# Voltage_Sensor.net
KiCad netlist of a schematic drawn in Altium Designer
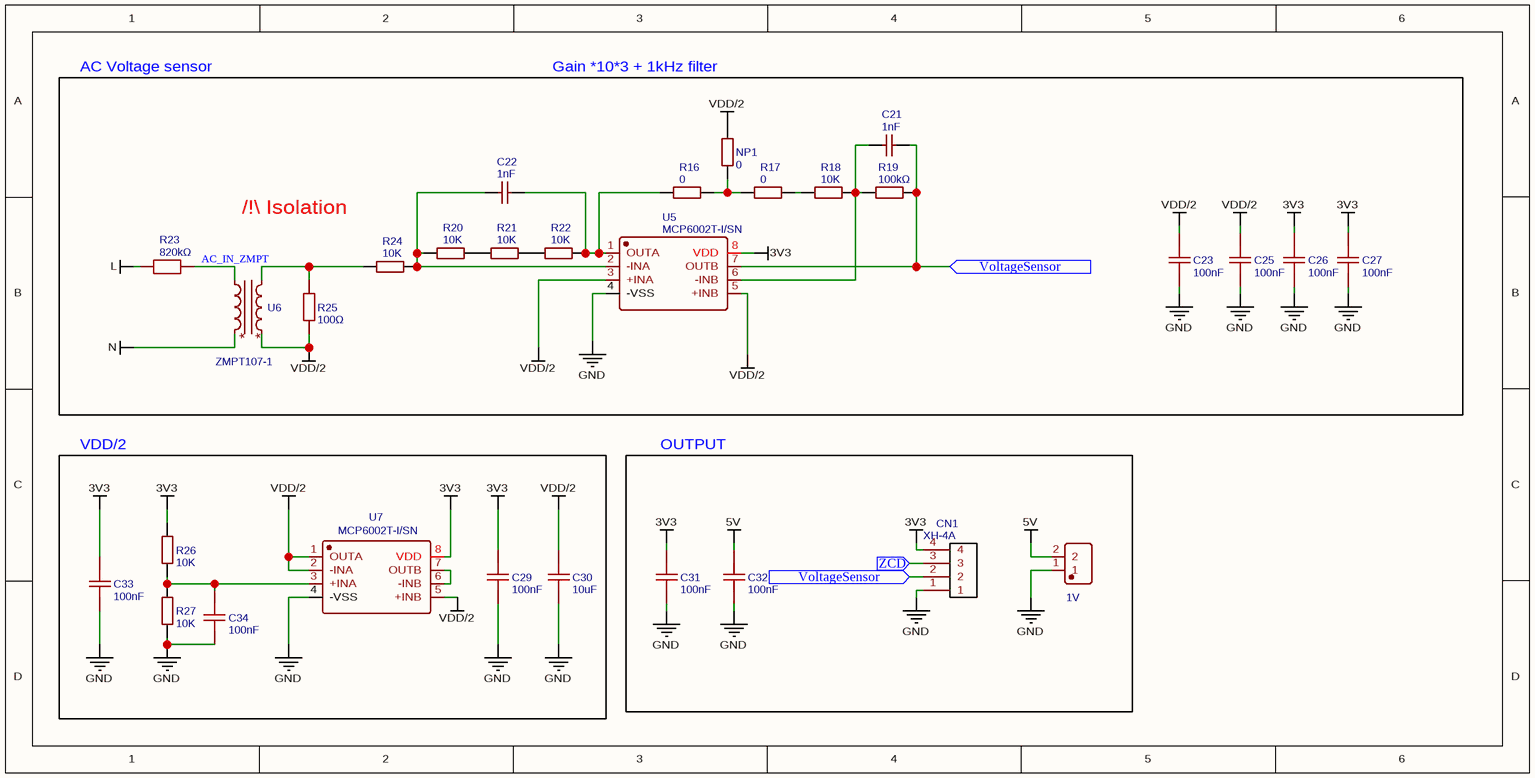
[diagram p0: Voltage Sensor.schdoc]

(export (version "E")
  (design (tool "Eeschema 10.0.6"))
  (components
    (comp (ref "1V")
      (value "XH-2A_C2908600")
      (fields
        (field (name "BOM_SUPPLIER PART") "C2908600")
        (field (name "BOM_MANUFACTURER PART") "XH-2A")
        (field (name "CONTRIBUTOR") "LCSC")
      )
      (libsource (lib "altium-import") (part "root_0_XH-2A_C2908600_"))
    )
    (comp (ref "C21")
      (value "1nF")
      (fields
        (field (name "BOM_MANUFACTURER PART") "CL10B102KB8NNNC")
        (field (name "BOM_SUPPLIER PART") "C1588")
      )
      (libsource (lib "altium-import") (part "root_0_1nF_"))
    )
    (comp (ref "C22")
      (value "1nF")
      (fields
        (field (name "BOM_MANUFACTURER PART") "CL10B102KB8NNNC")
        (field (name "BOM_SUPPLIER PART") "C1588")
      )
      (libsource (lib "altium-import") (part "root_0_1nF_"))
    )
    (comp (ref "C23")
      (value "100nF")
      (fields
        (field (name "BOM_MANUFACTURER PART") "CL10B104KB8NNNC")
        (field (name "BOM_SUPPLIER PART") "C1591")
      )
      (libsource (lib "altium-import") (part "root_3_100nF_"))
    )
    (comp (ref "C25")
      (value "100nF")
      (fields
        (field (name "BOM_MANUFACTURER PART") "CL10B104KB8NNNC")
        (field (name "BOM_SUPPLIER PART") "C1591")
      )
      (libsource (lib "altium-import") (part "root_3_100nF_"))
    )
    (comp (ref "C26")
      (value "100nF")
      (fields
        (field (name "BOM_MANUFACTURER PART") "CL10B104KB8NNNC")
        (field (name "BOM_SUPPLIER PART") "C1591")
      )
      (libsource (lib "altium-import") (part "root_3_100nF_"))
    )
    (comp (ref "C27")
      (value "100nF")
      (fields
        (field (name "BOM_MANUFACTURER PART") "CL10B104KB8NNNC")
        (field (name "BOM_SUPPLIER PART") "C1591")
      )
      (libsource (lib "altium-import") (part "root_3_100nF_"))
    )
    (comp (ref "C29")
      (value "100nF")
      (fields
        (field (name "BOM_MANUFACTURER PART") "CL10B104KB8NNNC")
        (field (name "BOM_SUPPLIER PART") "C1591")
      )
      (libsource (lib "altium-import") (part "root_3_100nF_"))
    )
    (comp (ref "C30")
      (value "10uF")
      (fields
        (field (name "BOM_MANUFACTURER PART") "0805F106M160NT")
        (field (name "BOM_SUPPLIER PART") "C90545")
      )
      (libsource (lib "altium-import") (part "root_1_10uF_"))
    )
    (comp (ref "C31")
      (value "100nF")
      (fields
        (field (name "BOM_MANUFACTURER PART") "CL10B104KB8NNNC")
        (field (name "BOM_SUPPLIER PART") "C1591")
      )
      (libsource (lib "altium-import") (part "root_3_100nF_"))
    )
    (comp (ref "C32")
      (value "100nF")
      (fields
        (field (name "BOM_MANUFACTURER PART") "CL10B104KB8NNNC")
        (field (name "BOM_SUPPLIER PART") "C1591")
      )
      (libsource (lib "altium-import") (part "root_3_100nF_"))
    )
    (comp (ref "C33")
      (value "100nF")
      (fields
        (field (name "BOM_MANUFACTURER PART") "CL10B104KB8NNNC")
        (field (name "BOM_SUPPLIER PART") "C1591")
      )
      (libsource (lib "altium-import") (part "root_3_100nF_"))
    )
    (comp (ref "C34")
      (value "100nF")
      (fields
        (field (name "BOM_MANUFACTURER PART") "CL10B104KB8NNNC")
        (field (name "BOM_SUPPLIER PART") "C1591")
      )
      (libsource (lib "altium-import") (part "root_3_100nF_"))
    )
    (comp (ref "CN1")
      (value "XH-4A")
      (fields (field (name "BOM_SUPPLIER PART") "C37815"))
      (libsource (lib "altium-import") (part "root_2_XH-4A_"))
    )
    (comp (ref "NP1")
      (value "0")
      (fields
        (field (name "BOM_MANUFACTURER PART") "RC0603JR-070RL")
        (field (name "BOM_SUPPLIER PART") "C95177")
      )
      (libsource (lib "altium-import") (part "root_1_0_"))
    )
    (comp (ref "R16")
      (value "0")
      (fields
        (field (name "BOM_MANUFACTURER PART") "RC0603JR-070RL")
        (field (name "BOM_SUPPLIER PART") "C95177")
      )
      (libsource (lib "altium-import") (part "root_0_0_"))
    )
    (comp (ref "R17")
      (value "0")
      (fields
        (field (name "BOM_MANUFACTURER PART") "RC0603JR-070RL")
        (field (name "BOM_SUPPLIER PART") "C95177")
      )
      (libsource (lib "altium-import") (part "root_0_0_"))
    )
    (comp (ref "R18")
      (value "10K")
      (fields
        (field (name "BOM_MANUFACTURER PART") "RC0603FR-0710KL")
        (field (name "BOM_SUPPLIER PART") "C98220")
      )
      (libsource (lib "altium-import") (part "root_0_10K_"))
    )
    (comp (ref "R19")
      (value "100kΩ")
      (fields
        (field (name "BOM_MANUFACTURER PART") "RTT031003FTP")
        (field (name "BOM_SUPPLIER PART") "C103200")
      )
      (libsource (lib "altium-import") (part "root_2_100kΩ_"))
    )
    (comp (ref "R20")
      (value "10K")
      (fields
        (field (name "BOM_MANUFACTURER PART") "RC0603FR-0710KL")
        (field (name "BOM_SUPPLIER PART") "C98220")
      )
      (libsource (lib "altium-import") (part "root_0_10K_"))
    )
    (comp (ref "R21")
      (value "10K")
      (fields
        (field (name "BOM_MANUFACTURER PART") "RC0603FR-0710KL")
        (field (name "BOM_SUPPLIER PART") "C98220")
      )
      (libsource (lib "altium-import") (part "root_0_10K_"))
    )
    (comp (ref "R22")
      (value "10K")
      (fields
        (field (name "BOM_MANUFACTURER PART") "RC0603FR-0710KL")
        (field (name "BOM_SUPPLIER PART") "C98220")
      )
      (libsource (lib "altium-import") (part "root_0_10K_"))
    )
    (comp (ref "R23")
      (value "820kΩ")
      (fields
        (field (name "BOM_SUPPLIER PART") "C414773")
        (field (name "BOM_MANUFACTURER PART") "HV06W4F8203T5E")
        (field (name "CONTRIBUTOR") "LCSC")
      )
      (libsource (lib "altium-import") (part "root_0_820kΩ_"))
    )
    (comp (ref "R24")
      (value "10K")
      (fields
        (field (name "BOM_MANUFACTURER PART") "RC0603FR-0710KL")
        (field (name "BOM_SUPPLIER PART") "C98220")
      )
      (libsource (lib "altium-import") (part "root_0_10K_"))
    )
    (comp (ref "R25")
      (value "100Ω")
      (fields
        (field (name "BOM_SUPPLIER PART") "C328334")
        (field (name "BOM_MANUFACTURER PART") "AECR0603F100RK9")
        (field (name "CONTRIBUTOR") "LCSC")
      )
      (libsource (lib "altium-import") (part "root_3_100Ω_"))
    )
    (comp (ref "R26")
      (value "10K")
      (fields
        (field (name "BOM_MANUFACTURER PART") "RC0603FR-0710KL")
        (field (name "BOM_SUPPLIER PART") "C98220")
      )
      (libsource (lib "altium-import") (part "root_1_10K_"))
    )
    (comp (ref "R27")
      (value "10K")
      (fields
        (field (name "BOM_MANUFACTURER PART") "RC0603FR-0710KL")
        (field (name "BOM_SUPPLIER PART") "C98220")
      )
      (libsource (lib "altium-import") (part "root_1_10K_"))
    )
    (comp (ref "U5")
      (value "MCP6002T-I/SN")
      (fields (field (name "BOM_SUPPLIER PART") "C7377"))
      (libsource (lib "altium-import") (part "root_0_MCP6002T-I/SN_"))
    )
    (comp (ref "U6")
      (value "ZMPT107-1")
      (fields (field (name "BOM_SUPPLIER PART") "C125191"))
      (libsource (lib "altium-import") (part "root_1_ZMPT107-1_"))
    )
    (comp (ref "U7")
      (value "MCP6002T-I/SN")
      (fields (field (name "BOM_SUPPLIER PART") "C7377"))
      (libsource (lib "altium-import") (part "root_0_MCP6002T-I/SN_"))
    )
  )
  (nets
    (net (code "1") (name "/AC_IN_ZMPT") (class "Default")
      (node (ref "R23") (pin "2") (pinfunction "2_2") (pintype "passive"))
      (node (ref "U6") (pin "2") (pinfunction "2_2") (pintype "passive"))
    )
    (net (code "2") (name "/VoltageSensor") (class "Default")
      (node (ref "C21") (pin "2") (pinfunction "2_2") (pintype "passive"))
      (node (ref "CN1") (pin "2") (pinfunction "2_2") (pintype "passive"))
      (node (ref "R19") (pin "1") (pinfunction "1_1") (pintype "passive"))
      (node (ref "U5") (pin "7") (pinfunction "OUTB_7") (pintype "passive"))
    )
    (net (code "3") (name "/ZCD") (class "Default")
      (node (ref "CN1") (pin "3") (pinfunction "3_3") (pintype "passive"))
    )
    (net (code "4") (name "3V3") (class "Default")
      (node (ref "C26") (pin "1") (pinfunction "1_1") (pintype "passive"))
      (node (ref "C27") (pin "1") (pinfunction "1_1") (pintype "passive"))
      (node (ref "C29") (pin "1") (pinfunction "1_1") (pintype "passive"))
      (node (ref "C31") (pin "1") (pinfunction "1_1") (pintype "passive"))
      (node (ref "C33") (pin "1") (pinfunction "1_1") (pintype "passive"))
      (node (ref "CN1") (pin "4") (pinfunction "4_4") (pintype "passive"))
      (node (ref "R26") (pin "2") (pinfunction "2_2") (pintype "passive"))
      (node (ref "U5") (pin "8") (pinfunction "VDD_8") (pintype "passive"))
      (node (ref "U7") (pin "8") (pinfunction "VDD_8") (pintype "passive"))
    )
    (net (code "5") (name "5V") (class "Default")
      (node (ref "1V") (pin "2") (pinfunction "2_2") (pintype "passive"))
      (node (ref "C32") (pin "1") (pinfunction "1_1") (pintype "passive"))
    )
    (net (code "6") (name "GND") (class "Default")
      (node (ref "1V") (pin "1") (pinfunction "1_1") (pintype "passive"))
      (node (ref "C23") (pin "2") (pinfunction "2_2") (pintype "passive"))
      (node (ref "C25") (pin "2") (pinfunction "2_2") (pintype "passive"))
      (node (ref "C26") (pin "2") (pinfunction "2_2") (pintype "passive"))
      (node (ref "C27") (pin "2") (pinfunction "2_2") (pintype "passive"))
      (node (ref "C29") (pin "2") (pinfunction "2_2") (pintype "passive"))
      (node (ref "C30") (pin "1") (pinfunction "1_1") (pintype "passive"))
      (node (ref "C31") (pin "2") (pinfunction "2_2") (pintype "passive"))
      (node (ref "C32") (pin "2") (pinfunction "2_2") (pintype "passive"))
      (node (ref "C33") (pin "2") (pinfunction "2_2") (pintype "passive"))
      (node (ref "C34") (pin "2") (pinfunction "2_2") (pintype "passive"))
      (node (ref "CN1") (pin "1") (pinfunction "1_1") (pintype "passive"))
      (node (ref "R27") (pin "1") (pinfunction "1_1") (pintype "passive"))
      (node (ref "U5") (pin "4") (pinfunction "-VSS_4") (pintype "passive"))
      (node (ref "U7") (pin "4") (pinfunction "-VSS_4") (pintype "passive"))
    )
    (net (code "7") (name "L") (class "Default")
      (node (ref "R23") (pin "1") (pinfunction "1_1") (pintype "passive"))
    )
    (net (code "8") (name "N") (class "Default")
      (node (ref "U6") (pin "1") (pinfunction "1_1") (pintype "passive"))
    )
    (net (code "9") (name "Net-(NP1-Pad1)") (class "Default")
      (node (ref "NP1") (pin "1") (pinfunction "1_1") (pintype "passive"))
      (node (ref "R16") (pin "2") (pinfunction "2_2") (pintype "passive"))
      (node (ref "R17") (pin "1") (pinfunction "1_1") (pintype "passive"))
    )
    (net (code "10") (name "Net-(R17-Pad2)") (class "Default")
      (node (ref "R17") (pin "2") (pinfunction "2_2") (pintype "passive"))
      (node (ref "R18") (pin "1") (pinfunction "1_1") (pintype "passive"))
    )
    (net (code "11") (name "Net-(R20-Pad2)") (class "Default")
      (node (ref "R20") (pin "2") (pinfunction "2_2") (pintype "passive"))
      (node (ref "R21") (pin "1") (pinfunction "1_1") (pintype "passive"))
    )
    (net (code "12") (name "Net-(R21-Pad2)") (class "Default")
      (node (ref "R21") (pin "2") (pinfunction "2_2") (pintype "passive"))
      (node (ref "R22") (pin "1") (pinfunction "1_1") (pintype "passive"))
    )
    (net (code "13") (name "Net-(R24-Pad1)") (class "Default")
      (node (ref "R24") (pin "1") (pinfunction "1_1") (pintype "passive"))
      (node (ref "R25") (pin "1") (pinfunction "1_1") (pintype "passive"))
      (node (ref "U6") (pin "4") (pinfunction "4_4") (pintype "passive"))
    )
    (net (code "14") (name "Net-(U5--INA)") (class "Default")
      (node (ref "C22") (pin "1") (pinfunction "1_1") (pintype "passive"))
      (node (ref "R20") (pin "1") (pinfunction "1_1") (pintype "passive"))
      (node (ref "R24") (pin "2") (pinfunction "2_2") (pintype "passive"))
      (node (ref "U5") (pin "2") (pinfunction "-INA_2") (pintype "passive"))
    )
    (net (code "15") (name "Net-(U5--INB)") (class "Default")
      (node (ref "C21") (pin "1") (pinfunction "1_1") (pintype "passive"))
      (node (ref "R18") (pin "2") (pinfunction "2_2") (pintype "passive"))
      (node (ref "R19") (pin "2") (pinfunction "2_2") (pintype "passive"))
      (node (ref "U5") (pin "6") (pinfunction "-INB_6") (pintype "passive"))
    )
    (net (code "16") (name "Net-(U5-OUTA)") (class "Default")
      (node (ref "C22") (pin "2") (pinfunction "2_2") (pintype "passive"))
      (node (ref "R16") (pin "1") (pinfunction "1_1") (pintype "passive"))
      (node (ref "R22") (pin "2") (pinfunction "2_2") (pintype "passive"))
      (node (ref "U5") (pin "1") (pinfunction "OUTA_1") (pintype "passive"))
    )
    (net (code "17") (name "Net-(U7-+INA)") (class "Default")
      (node (ref "C34") (pin "1") (pinfunction "1_1") (pintype "passive"))
      (node (ref "R26") (pin "1") (pinfunction "1_1") (pintype "passive"))
      (node (ref "R27") (pin "2") (pinfunction "2_2") (pintype "passive"))
      (node (ref "U7") (pin "3") (pinfunction "+INA_3") (pintype "passive"))
    )
    (net (code "18") (name "Net-(U7--INB)") (class "Default")
      (node (ref "U7") (pin "6") (pinfunction "-INB_6") (pintype "passive"))
      (node (ref "U7") (pin "7") (pinfunction "OUTB_7") (pintype "passive"))
    )
    (net (code "19") (name "VDD{slash}2") (class "Default")
      (node (ref "C23") (pin "1") (pinfunction "1_1") (pintype "passive"))
      (node (ref "C25") (pin "1") (pinfunction "1_1") (pintype "passive"))
      (node (ref "C30") (pin "2") (pinfunction "2_2") (pintype "passive"))
      (node (ref "NP1") (pin "2") (pinfunction "2_2") (pintype "passive"))
      (node (ref "R25") (pin "2") (pinfunction "2_2") (pintype "passive"))
      (node (ref "U5") (pin "3") (pinfunction "+INA_3") (pintype "passive"))
      (node (ref "U5") (pin "5") (pinfunction "+INB_5") (pintype "passive"))
      (node (ref "U6") (pin "3") (pinfunction "3_3") (pintype "passive"))
      (node (ref "U7") (pin "1") (pinfunction "OUTA_1") (pintype "passive"))
      (node (ref "U7") (pin "2") (pinfunction "-INA_2") (pintype "passive"))
      (node (ref "U7") (pin "5") (pinfunction "+INB_5") (pintype "passive"))
    )
  )
)
